# QCPower_Rev_A_Sht1_Logic_Connector.net
KiCad netlist of a schematic drawn in Altium Designer
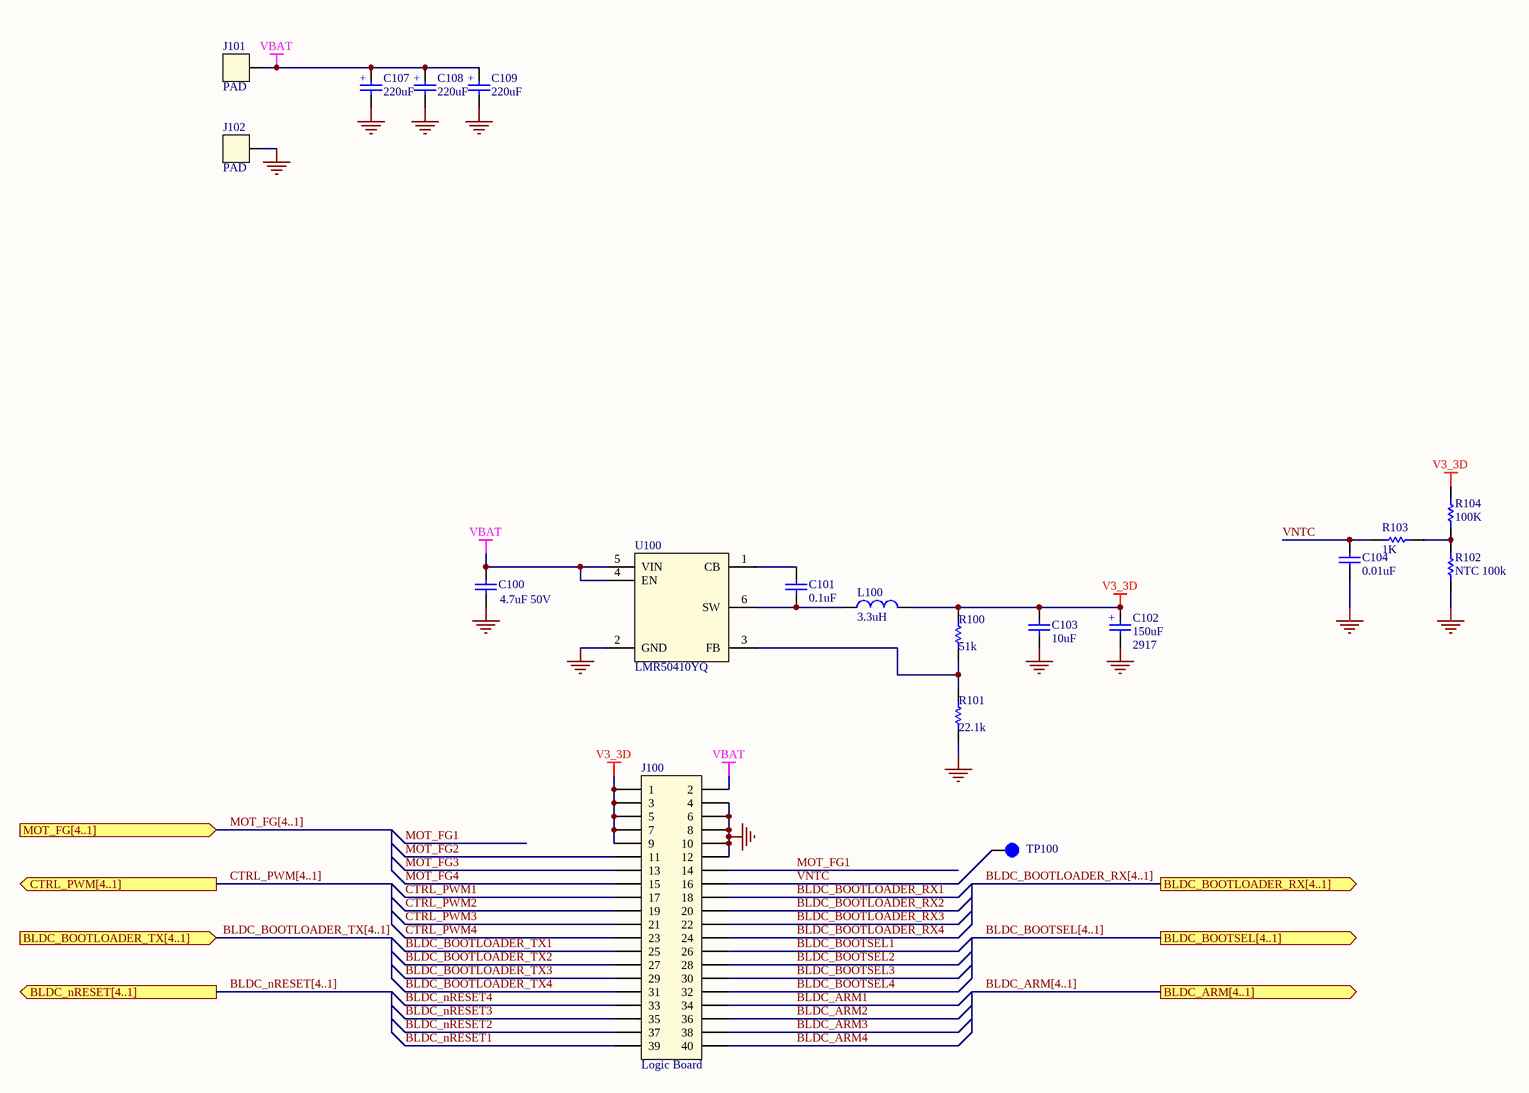
[diagram p0: QCPower Rev A Sht1 Logic Connector.SchDoc]

(export (version "E")
  (design (tool "Eeschema 10.0.6"))
  (components
    (comp (ref "C100")
      (value "4.7uF 50V")
      (footprint "SMD CAP 0805")
      (description "CAP CER 4.7UF 50V X5R 0805")
      (fields (field (name "2. MANUFACTURER PART NUMBER") "CL21A475KBQNNNE"))
      (libsource (lib "SBCLib") (part "CAP MLCC SMD"))
    )
    (comp (ref "C101")
      (value "0.1uF")
      (footprint "SMD CAP 0402")
      (description "CAP CER 0.1UF 25V X7R 0402")
      (fields (field (name "2. MANUFACTURER PART NUMBER") "CC0402KRX7R8BB104"))
      (libsource (lib "SBCLib") (part "CAP MLCC SMD"))
    )
    (comp (ref "C102")
      (value "150uF")
      (footprint "SMD CAP TANT 2917")
      (description "CAP TANT 150UF 10% 10V 2917")
      (fields
        (field (name "2. MANUFACTURER PART NUMBER") "T495D157K010ATE100")
        (field (name "4. PACKAGE") "2917")
      )
      (libsource (lib "SBCLib") (part "CAP POL"))
    )
    (comp (ref "C103")
      (value "10uF")
      (footprint "SMD CAP 0805")
      (description "CAP CER 10UF 25V X5R 0805")
      (fields (field (name "2. MANUFACTURER PART NUMBER") "TMK212BBJ106KG-T"))
      (libsource (lib "SBCLib") (part "CAP MLCC SMD"))
    )
    (comp (ref "C104")
      (value "0.01uF")
      (footprint "SMD CAP 0402")
      (description "CAP CER 10000PF 16V X7R 0402")
      (fields (field (name "2. MANUFACTURER PART NUMBER") "0402B103K160CT"))
      (libsource (lib "SBCLib") (part "CAP MLCC SMD"))
    )
    (comp (ref "C107")
      (value "220uF")
      (footprint "POLARIZED CAP THROUGH HOLE SIDE MOUNT")
      (description "CAP ALUM 220UF 20% 63V RADIAL")
      (fields (field (name "2. MANUFACTURER PART NUMBER") "UCD1J221MNQ1MS"))
      (libsource (lib "SBCLib") (part "CAP POL"))
    )
    (comp (ref "C108")
      (value "220uF")
      (footprint "POLARIZED CAP THROUGH HOLE SIDE MOUNT")
      (description "CAP ALUM 220UF 20% 63V RADIAL")
      (fields (field (name "2. MANUFACTURER PART NUMBER") "ECA-1JM221"))
      (libsource (lib "SBCLib") (part "CAP POL"))
    )
    (comp (ref "C109")
      (value "220uF")
      (footprint "POLARIZED CAP THROUGH HOLE SIDE MOUNT")
      (description "CAP ALUM 220UF 20% 63V RADIAL")
      (fields (field (name "2. MANUFACTURER PART NUMBER") "UCD1J221MNQ1MS"))
      (libsource (lib "SBCLib") (part "CAP POL"))
    )
    (comp (ref "J100")
      (value "Logic Board")
      (footprint "CONN QCOPTER LOGIC Rev A")
      (description "CONN QCOPTER LOGIC REV A")
      (fields (field (name "2. MANUFACTURER PART NUMBER") "‎10144518-041802LF‎"))
      (libsource (lib "SBCLib") (part "CONN QCOPTER LOGIC REV A"))
    )
    (comp (ref "J101")
      (value "PAD")
      (footprint "CONN SOLDER MOTOR")
      (description "CONN SOLDER MOTOR 7x5")
      (libsource (lib "SBCLib") (part "CONN SOLDER MOTOR 7x5"))
    )
    (comp (ref "J102")
      (value "PAD")
      (footprint "CONN SOLDER MOTOR")
      (description "CONN SOLDER MOTOR 7x5")
      (libsource (lib "SBCLib") (part "CONN SOLDER MOTOR 7x5"))
    )
    (comp (ref "L100")
      (value "3.3uH")
      (footprint "IND SMD 0806")
      (description "FIXED IND 3.3UH 1.2A 150 MOHM")
      (fields (field (name "2. MANUFACTURER PART NUMBER") "LQM2MPN3R3NG0L"))
      (libsource (lib "SBCLib") (part "INDUCTOR"))
    )
    (comp (ref "R100")
      (value "51k")
      (footprint "SMD RES 0402")
      (description "RES SMD 51K OHM 1% 1/16W 0402")
      (fields (field (name "2. MANUFACTURER PART NUMBER") "RC0402FR-0751KL"))
      (libsource (lib "SBCLib") (part "RES SMD"))
    )
    (comp (ref "R101")
      (value "22.1k")
      (footprint "SMD RES 0402")
      (description "RES SMD 22.1K OHM 1% 1/16W 0402")
      (fields (field (name "2. MANUFACTURER PART NUMBER") "RC0402FR-0722K1L"))
      (libsource (lib "SBCLib") (part "RES SMD"))
    )
    (comp (ref "R102")
      (value "NTC 100k")
      (footprint "SMD RES 0402")
      (description "NTC,100K,1%,0402,AEC-Q200,EPOXY")
      (fields (field (name "2. MANUFACTURER PART NUMBER") "NTCSP104KF104FT1S"))
      (libsource (lib "SBCLib") (part "RES SMD"))
    )
    (comp (ref "R103")
      (value "1K")
      (footprint "SMD RES 0402")
      (description "RES SMD 1K OHM 1% 1/16W 0402")
      (fields (field (name "2. MANUFACTURER PART NUMBER") "RC0402FR-071KL"))
      (libsource (lib "SBCLib") (part "RES SMD"))
    )
    (comp (ref "R104")
      (value "100K")
      (footprint "SMD RES 0402")
      (description "RES SMD 100K OHM 1% 1/16W 0402")
      (fields (field (name "2. MANUFACTURER PART NUMBER") "RC0402FR-07100KL"))
      (libsource (lib "SBCLib") (part "RES SMD"))
    )
    (comp (ref "TP100")
      (value "TESTPOINT SMD")
      (footprint "TESTPOINT 1mm DIA")
      (description "TESTPOINT SMD PAD")
      (libsource (lib "SBCLib") (part "TESTPOINT PAD"))
    )
    (comp (ref "U100")
      (value "LMR50410YQ")
      (footprint "SOT-23-6")
      (description "IC REG BUCK 1A SOT-23-6")
      (fields (field (name "2. MANUFACTURER PART NUMBER") "LMR50410YQDBVRQ1"))
      (libsource (lib "SBCLib") (part "IC REG BUCK 1A SOT-23-6"))
    )
  )
  (nets
    (net (code "1") (name "/BLDC_ARM1") (class "Default")
      (node (ref "J100") (pin "34") (pinfunction "34_34") (pintype "passive"))
    )
    (net (code "2") (name "/BLDC_ARM2") (class "Default")
      (node (ref "J100") (pin "36") (pinfunction "36_36") (pintype "passive"))
    )
    (net (code "3") (name "/BLDC_ARM3") (class "Default")
      (node (ref "J100") (pin "38") (pinfunction "38_38") (pintype "passive"))
    )
    (net (code "4") (name "/BLDC_ARM4") (class "Default")
      (node (ref "J100") (pin "40") (pinfunction "40_40") (pintype "passive"))
    )
    (net (code "6") (name "/BLDC_BOOTLOADER_RX1") (class "Default")
      (node (ref "J100") (pin "18") (pinfunction "18_18") (pintype "passive"))
    )
    (net (code "7") (name "/BLDC_BOOTLOADER_RX2") (class "Default")
      (node (ref "J100") (pin "20") (pinfunction "20_20") (pintype "passive"))
    )
    (net (code "8") (name "/BLDC_BOOTLOADER_RX3") (class "Default")
      (node (ref "J100") (pin "22") (pinfunction "22_22") (pintype "passive"))
    )
    (net (code "9") (name "/BLDC_BOOTLOADER_RX4") (class "Default")
      (node (ref "J100") (pin "24") (pinfunction "24_24") (pintype "passive"))
    )
    (net (code "11") (name "/BLDC_BOOTLOADER_TX1") (class "Default")
      (node (ref "J100") (pin "25") (pinfunction "25_25") (pintype "passive"))
    )
    (net (code "12") (name "/BLDC_BOOTLOADER_TX2") (class "Default")
      (node (ref "J100") (pin "27") (pinfunction "27_27") (pintype "passive"))
    )
    (net (code "13") (name "/BLDC_BOOTLOADER_TX3") (class "Default")
      (node (ref "J100") (pin "29") (pinfunction "29_29") (pintype "passive"))
    )
    (net (code "14") (name "/BLDC_BOOTLOADER_TX4") (class "Default")
      (node (ref "J100") (pin "31") (pinfunction "31_31") (pintype "passive"))
    )
    (net (code "16") (name "/BLDC_BOOTSEL1") (class "Default")
      (node (ref "J100") (pin "26") (pinfunction "26_26") (pintype "passive"))
    )
    (net (code "17") (name "/BLDC_BOOTSEL2") (class "Default")
      (node (ref "J100") (pin "28") (pinfunction "28_28") (pintype "passive"))
    )
    (net (code "18") (name "/BLDC_BOOTSEL3") (class "Default")
      (node (ref "J100") (pin "30") (pinfunction "30_30") (pintype "passive"))
    )
    (net (code "19") (name "/BLDC_BOOTSEL4") (class "Default")
      (node (ref "J100") (pin "32") (pinfunction "32_32") (pintype "passive"))
    )
    (net (code "21") (name "/BLDC_nRESET1") (class "Default")
      (node (ref "J100") (pin "39") (pinfunction "39_39") (pintype "passive"))
    )
    (net (code "22") (name "/BLDC_nRESET2") (class "Default")
      (node (ref "J100") (pin "37") (pinfunction "37_37") (pintype "passive"))
    )
    (net (code "23") (name "/BLDC_nRESET3") (class "Default")
      (node (ref "J100") (pin "35") (pinfunction "35_35") (pintype "passive"))
    )
    (net (code "24") (name "/BLDC_nRESET4") (class "Default")
      (node (ref "J100") (pin "33") (pinfunction "33_33") (pintype "passive"))
    )
    (net (code "26") (name "/CTRL_PWM1") (class "Default")
      (node (ref "J100") (pin "17") (pinfunction "17_17") (pintype "passive"))
    )
    (net (code "27") (name "/CTRL_PWM2") (class "Default")
      (node (ref "J100") (pin "19") (pinfunction "19_19") (pintype "passive"))
    )
    (net (code "28") (name "/CTRL_PWM3") (class "Default")
      (node (ref "J100") (pin "21") (pinfunction "21_21") (pintype "passive"))
    )
    (net (code "29") (name "/CTRL_PWM4") (class "Default")
      (node (ref "J100") (pin "23") (pinfunction "23_23") (pintype "passive"))
    )
    (net (code "31") (name "/MOT_FG1") (class "Default")
      (node (ref "J100") (pin "14") (pinfunction "14_14") (pintype "passive"))
    )
    (net (code "32") (name "/MOT_FG2") (class "Default")
      (node (ref "J100") (pin "11") (pinfunction "11_11") (pintype "passive"))
    )
    (net (code "33") (name "/MOT_FG3") (class "Default")
      (node (ref "J100") (pin "13") (pinfunction "13_13") (pintype "passive"))
    )
    (net (code "34") (name "/MOT_FG4") (class "Default")
      (node (ref "J100") (pin "15") (pinfunction "15_15") (pintype "passive"))
    )
    (net (code "36") (name "/VNTC") (class "Default")
      (node (ref "C104") (pin "1") (pinfunction "1_1") (pintype "passive"))
      (node (ref "J100") (pin "16") (pinfunction "16_16") (pintype "passive"))
      (node (ref "R103") (pin "2") (pinfunction "2_2") (pintype "passive"))
      (node (ref "TP100") (pin "1") (pinfunction "1_1") (pintype "passive"))
    )
    (net (code "37") (name "GND") (class "Default")
      (node (ref "C100") (pin "2") (pinfunction "2_2") (pintype "passive"))
      (node (ref "C102") (pin "2") (pinfunction "2_2") (pintype "passive"))
      (node (ref "C103") (pin "2") (pinfunction "2_2") (pintype "passive"))
      (node (ref "C104") (pin "2") (pinfunction "2_2") (pintype "passive"))
      (node (ref "C107") (pin "2") (pinfunction "2_2") (pintype "passive"))
      (node (ref "C108") (pin "2") (pinfunction "2_2") (pintype "passive"))
      (node (ref "C109") (pin "2") (pinfunction "2_2") (pintype "passive"))
      (node (ref "J100") (pin "10") (pinfunction "10_10") (pintype "passive"))
      (node (ref "J100") (pin "12") (pinfunction "12_12") (pintype "passive"))
      (node (ref "J100") (pin "4") (pinfunction "4_4") (pintype "passive"))
      (node (ref "J100") (pin "6") (pinfunction "6_6") (pintype "passive"))
      (node (ref "J100") (pin "8") (pinfunction "8_8") (pintype "passive"))
      (node (ref "J102") (pin "1") (pinfunction "1_1") (pintype "passive"))
      (node (ref "R101") (pin "2") (pinfunction "2_2") (pintype "passive"))
      (node (ref "R102") (pin "2") (pinfunction "2_2") (pintype "passive"))
      (node (ref "U100") (pin "2") (pinfunction "GND_2") (pintype "passive"))
    )
    (net (code "38") (name "Net-(R102-Pad1)") (class "Default")
      (node (ref "R102") (pin "1") (pinfunction "1_1") (pintype "passive"))
      (node (ref "R103") (pin "1") (pinfunction "1_1") (pintype "passive"))
      (node (ref "R104") (pin "2") (pinfunction "2_2") (pintype "passive"))
    )
    (net (code "39") (name "Net-(U100-CB)") (class "Default")
      (node (ref "C101") (pin "2") (pinfunction "2_2") (pintype "passive"))
      (node (ref "U100") (pin "1") (pinfunction "CB_1") (pintype "passive"))
    )
    (net (code "40") (name "Net-(U100-FB)") (class "Default")
      (node (ref "R100") (pin "2") (pinfunction "2_2") (pintype "passive"))
      (node (ref "R101") (pin "1") (pinfunction "1_1") (pintype "passive"))
      (node (ref "U100") (pin "3") (pinfunction "FB_3") (pintype "passive"))
    )
    (net (code "41") (name "Net-(U100-SW)") (class "Default")
      (node (ref "C101") (pin "1") (pinfunction "1_1") (pintype "passive"))
      (node (ref "L100") (pin "1") (pinfunction "1_1") (pintype "passive"))
      (node (ref "U100") (pin "6") (pinfunction "SW_6") (pintype "passive"))
    )
    (net (code "42") (name "V3_3D") (class "Default")
      (node (ref "C102") (pin "1") (pinfunction "1_1") (pintype "passive"))
      (node (ref "C103") (pin "1") (pinfunction "1_1") (pintype "passive"))
      (node (ref "J100") (pin "1") (pinfunction "1_1") (pintype "passive"))
      (node (ref "J100") (pin "3") (pinfunction "3_3") (pintype "passive"))
      (node (ref "J100") (pin "5") (pinfunction "5_5") (pintype "passive"))
      (node (ref "J100") (pin "7") (pinfunction "7_7") (pintype "passive"))
      (node (ref "J100") (pin "9") (pinfunction "9_9") (pintype "passive"))
      (node (ref "L100") (pin "2") (pinfunction "2_2") (pintype "passive"))
      (node (ref "R100") (pin "1") (pinfunction "1_1") (pintype "passive"))
      (node (ref "R104") (pin "1") (pinfunction "1_1") (pintype "passive"))
    )
    (net (code "43") (name "VBAT") (class "Default")
      (node (ref "C100") (pin "1") (pinfunction "1_1") (pintype "passive"))
      (node (ref "C107") (pin "1") (pinfunction "1_1") (pintype "passive"))
      (node (ref "C108") (pin "1") (pinfunction "1_1") (pintype "passive"))
      (node (ref "C109") (pin "1") (pinfunction "1_1") (pintype "passive"))
      (node (ref "J100") (pin "2") (pinfunction "2_2") (pintype "passive"))
      (node (ref "J101") (pin "1") (pinfunction "1_1") (pintype "passive"))
      (node (ref "U100") (pin "4") (pinfunction "EN_4") (pintype "passive"))
      (node (ref "U100") (pin "5") (pinfunction "VIN_5") (pintype "passive"))
    )
  )
)
